# Mini_Arduino_4mm_Oval.net
KiCad netlist of a schematic drawn in EAGLE
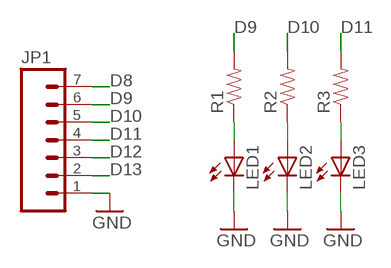
[diagram p0: schematic, sheet 1]

(export (version "E")
  (design (tool "Eeschema 10.0.6"))
  (components
    (comp (ref "JP1")
      (value "M07")
      (footprint "eagle-import:1X07")
      (libsource (lib "eagle-import") (part "M07"))
    )
    (comp (ref "LED1")
      (value "LEDOVAL")
      (footprint "eagle-import:LED-OVAL")
      (libsource (lib "eagle-import") (part "LEDOVAL"))
    )
    (comp (ref "LED2")
      (value "LEDOVAL")
      (footprint "eagle-import:LED-OVAL")
      (libsource (lib "eagle-import") (part "LEDOVAL"))
    )
    (comp (ref "LED3")
      (value "LEDOVAL")
      (footprint "eagle-import:LED-OVAL")
      (libsource (lib "eagle-import") (part "LEDOVAL"))
    )
    (comp (ref "R1")
      (value "RESISTORAXIAL-0.3")
      (footprint "eagle-import:AXIAL-0.3")
      (libsource (lib "eagle-import") (part "RESISTORAXIAL-0.3"))
    )
    (comp (ref "R2")
      (value "RESISTORAXIAL-0.3")
      (footprint "eagle-import:AXIAL-0.3")
      (libsource (lib "eagle-import") (part "RESISTORAXIAL-0.3"))
    )
    (comp (ref "R3")
      (value "RESISTORAXIAL-0.3")
      (footprint "eagle-import:AXIAL-0.3")
      (libsource (lib "eagle-import") (part "RESISTORAXIAL-0.3"))
    )
  )
  (nets
    (net (code "1") (name "/D8") (class "Default")
      (node (ref "JP1") (pin "7") (pinfunction "7_7") (pintype "passive"))
    )
    (net (code "2") (name "/D9") (class "Default")
      (node (ref "JP1") (pin "6") (pinfunction "6_6") (pintype "passive"))
      (node (ref "R1") (pin "P$2") (pinfunction "2_P$2") (pintype "passive"))
    )
    (net (code "3") (name "/D10") (class "Default")
      (node (ref "JP1") (pin "5") (pinfunction "5_5") (pintype "passive"))
      (node (ref "R2") (pin "P$2") (pinfunction "2_P$2") (pintype "passive"))
    )
    (net (code "4") (name "/D11") (class "Default")
      (node (ref "JP1") (pin "4") (pinfunction "4_4") (pintype "passive"))
      (node (ref "R3") (pin "P$2") (pinfunction "2_P$2") (pintype "passive"))
    )
    (net (code "5") (name "/D12") (class "Default")
      (node (ref "JP1") (pin "3") (pinfunction "3_3") (pintype "passive"))
    )
    (net (code "6") (name "/D13") (class "Default")
      (node (ref "JP1") (pin "2") (pinfunction "2_2") (pintype "passive"))
    )
    (net (code "7") (name "GND") (class "Default")
      (node (ref "JP1") (pin "1") (pinfunction "1_1") (pintype "passive"))
      (node (ref "LED1") (pin "CATHODE") (pinfunction "C_CATHODE") (pintype "passive"))
      (node (ref "LED2") (pin "CATHODE") (pinfunction "C_CATHODE") (pintype "passive"))
      (node (ref "LED3") (pin "CATHODE") (pinfunction "C_CATHODE") (pintype "passive"))
    )
    (net (code "8") (name "Net-(LED1-A)") (class "Default")
      (node (ref "LED1") (pin "ANODE") (pinfunction "A_ANODE") (pintype "passive"))
      (node (ref "R1") (pin "P$1") (pinfunction "1_P$1") (pintype "passive"))
    )
    (net (code "9") (name "Net-(LED2-A)") (class "Default")
      (node (ref "LED2") (pin "ANODE") (pinfunction "A_ANODE") (pintype "passive"))
      (node (ref "R2") (pin "P$1") (pinfunction "1_P$1") (pintype "passive"))
    )
    (net (code "10") (name "Net-(LED3-A)") (class "Default")
      (node (ref "LED3") (pin "ANODE") (pinfunction "A_ANODE") (pintype "passive"))
      (node (ref "R3") (pin "P$1") (pinfunction "1_P$1") (pintype "passive"))
    )
  )
)
